# Power.net
KiCad netlist of a schematic drawn in Altium Designer
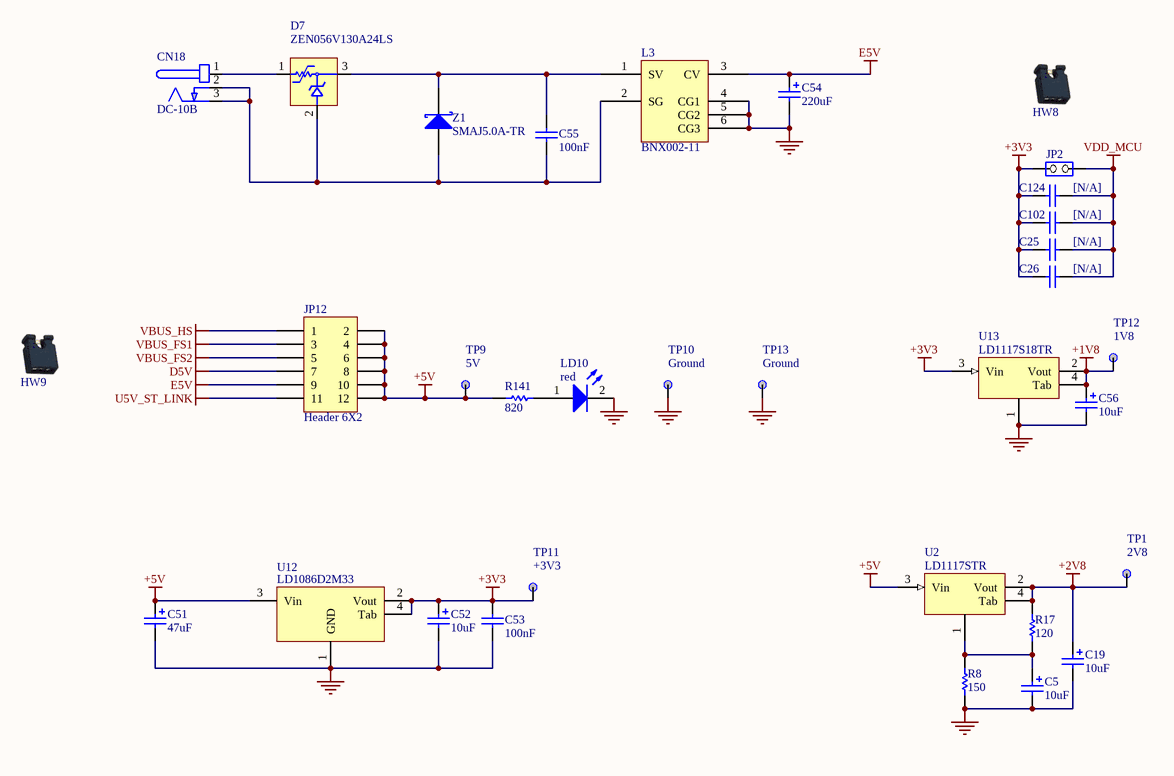
[diagram p0: Power.SchDoc]

(export (version "E")
  (design (tool "Eeschema 10.0.6"))
  (components
    (comp (ref "C5")
      (value "10uF")
      (footprint "TAN-A")
      (description "Polarized Capacitor (Radial)")
      (fields (field (name "PUBLISHER") "Altium Limited"))
      (libsource (lib "Miscellaneous Devices") (part "Cap Pol1"))
    )
    (comp (ref "C19")
      (value "10uF")
      (footprint "TAN-A")
      (description "Polarized Capacitor (Radial)")
      (fields (field (name "PUBLISHER") "Altium Limited"))
      (libsource (lib "Miscellaneous Devices") (part "Cap Pol1"))
    )
    (comp (ref "C25")
      (value "[N/A]")
      (footprint "0603C")
      (description "Capacitor")
      (fields (field (name "PUBLISHER") "Altium Limited"))
      (libsource (lib "Miscellaneous Devices") (part "Cap"))
    )
    (comp (ref "C26")
      (value "[N/A]")
      (footprint "0603C")
      (description "Capacitor")
      (fields (field (name "PUBLISHER") "Altium Limited"))
      (libsource (lib "Miscellaneous Devices") (part "Cap"))
    )
    (comp (ref "C51")
      (value "47uF")
      (footprint "CAE_5R3X5R3_H5R4")
      (description "Polarized Capacitor (Radial)")
      (fields (field (name "PUBLISHER") "Altium Limited"))
      (libsource (lib "Miscellaneous Devices") (part "Cap Pol1"))
    )
    (comp (ref "C52")
      (value "10uF")
      (footprint "TAN-A")
      (description "Polarized Capacitor (Radial)")
      (fields (field (name "PUBLISHER") "Altium Limited"))
      (libsource (lib "Miscellaneous Devices") (part "Cap Pol1"))
    )
    (comp (ref "C53")
      (value "100nF")
      (footprint "0603C")
      (description "Capacitor")
      (fields (field (name "PUBLISHER") "Altium Limited"))
      (libsource (lib "Miscellaneous Devices") (part "Cap"))
    )
    (comp (ref "C54")
      (value "220uF")
      (footprint "c310m-6")
      (description "Polarized Capacitor (Radial)")
      (fields (field (name "PUBLISHER") "Altium Limited"))
      (libsource (lib "Miscellaneous Devices") (part "Cap Pol1"))
    )
    (comp (ref "C55")
      (value "100nF")
      (footprint "0603C")
      (description "Capacitor")
      (fields (field (name "PUBLISHER") "Altium Limited"))
      (libsource (lib "Miscellaneous Devices") (part "CAP"))
    )
    (comp (ref "C56")
      (value "10uF")
      (footprint "TAN-A")
      (description "Polarized Capacitor (Radial)")
      (fields (field (name "PUBLISHER") "Altium Limited"))
      (libsource (lib "Miscellaneous Devices") (part "Cap Pol1"))
    )
    (comp (ref "C102")
      (value "[N/A]")
      (footprint "0603C")
      (description "Capacitor")
      (fields (field (name "PUBLISHER") "Altium Limited"))
      (libsource (lib "Miscellaneous Devices") (part "Cap"))
    )
    (comp (ref "C124")
      (value "[N/A]")
      (footprint "0603C")
      (description "Capacitor")
      (fields (field (name "PUBLISHER") "Altium Limited"))
      (libsource (lib "Miscellaneous Devices") (part "Cap"))
    )
    (comp (ref "CN18")
      (value "DC-10B")
      (footprint "PWR_JACK_DC10")
      (libsource (lib "STR910_SCHLIB") (part "PJ202A"))
    )
    (comp (ref "D7")
      (value "ZEN056V130A24LS")
      (footprint "TYCO_ZEN056V130A24LS")
      (libsource (lib "STR910_SCHLIB") (part "ZEN056V130A24LS"))
    )
    (comp (ref "HW8") (value "JUMPER_OPEN") (libsource (lib "mb1045") (part "JUMPER_OPEN")))
    (comp (ref "HW9") (value "JUMPER_OPEN") (libsource (lib "mb1045") (part "JUMPER_OPEN")))
    (comp (ref "JP2") (value "~") (footprint "SIP2") (libsource (lib "*") (part "JP2")))
    (comp (ref "JP12")
      (value "Header 6X2")
      (footprint "HDR_2X6_2R54")
      (description "Header, 6-Pin, Dual row")
      (fields (field (name "PUBLISHER") "Altium Limited"))
      (libsource (lib "mb1045") (part "Header 6X2"))
    )
    (comp (ref "L3")
      (value "BNX002-11")
      (footprint "BNX001")
      (description "Inductor, DC power EMI line filter, 40dB min (1MHz - 1GHz) insertion loss")
      (libsource (lib "STR910_SCHLIB") (part "BNX002"))
    )
    (comp (ref "LD10")
      (value "red")
      (footprint "0603D")
      (description "Typical RED, GREEN, YELLOW, AMBER GaAs LED")
      (fields (field (name "PUBLISHER") "Altium Limited"))
      (libsource (lib "Miscellaneous Devices") (part "LED2"))
    )
    (comp (ref "R8")
      (value "150")
      (footprint "0603R")
      (description "Resistor")
      (fields (field (name "PUBLISHER") "Altium Limited"))
      (libsource (lib "Miscellaneous Devices") (part "res1"))
    )
    (comp (ref "R17")
      (value "120")
      (footprint "0603R")
      (description "Resistor")
      (fields (field (name "PUBLISHER") "Altium Limited"))
      (libsource (lib "Miscellaneous Devices") (part "res1"))
    )
    (comp (ref "R141")
      (value "820")
      (footprint "0603R")
      (description "Resistor")
      (fields (field (name "PUBLISHER") "Altium Limited"))
      (libsource (lib "Miscellaneous Devices") (part "res1"))
    )
    (comp (ref "TP1") (value "2V8") (footprint "TP") (libsource (lib "*") (part "TP")))
    (comp (ref "TP9") (value "5V") (footprint "TP") (libsource (lib "*") (part "TP")))
    (comp (ref "TP10") (value "Ground") (footprint "TP") (libsource (lib "*") (part "TP")))
    (comp (ref "TP11") (value "+3V3") (footprint "TP") (libsource (lib "*") (part "TP")))
    (comp (ref "TP12") (value "1V8") (footprint "TP") (libsource (lib "*") (part "TP")))
    (comp (ref "TP13") (value "Ground") (footprint "TP") (libsource (lib "*") (part "TP")))
    (comp (ref "U2") (value "LD1117STR") (footprint "SOT-223") (libsource (lib "mb1045") (part "LD1117")))
    (comp (ref "U12")
      (value "LD1086D2M33")
      (footprint "TO263-3")
      (libsource (lib "mb1045") (part "VOLTREG1"))
    )
    (comp (ref "U13") (value "LD1117S18TR") (footprint "SOT-223") (libsource (lib "mb1045") (part "LD1117")))
    (comp (ref "Z1")
      (value "SMAJ5.0A-TR")
      (footprint "sma")
      (description "Schottky Diode")
      (fields (field (name "PUBLISHER") "Altium Limited"))
      (libsource (lib "Miscellaneous Devices") (part "D Schottky"))
    )
  )
  (nets
    (net (code "1") (name "+1V8") (class "Default")
      (node (ref "C56") (pin "1") (pinfunction "1_1") (pintype "passive"))
      (node (ref "TP12") (pin "1") (pinfunction "1_1") (pintype "passive"))
      (node (ref "U13") (pin "2") (pinfunction "Vout_2") (pintype "power_in"))
      (node (ref "U13") (pin "4") (pinfunction "Tab_4") (pintype "power_in"))
    )
    (net (code "2") (name "+2V8") (class "Default")
      (node (ref "C19") (pin "1") (pinfunction "1_1") (pintype "passive"))
      (node (ref "R17") (pin "1") (pinfunction "1_1") (pintype "passive"))
      (node (ref "TP1") (pin "1") (pinfunction "1_1") (pintype "passive"))
      (node (ref "U2") (pin "2") (pinfunction "Vout_2") (pintype "power_in"))
      (node (ref "U2") (pin "4") (pinfunction "Tab_4") (pintype "power_in"))
    )
    (net (code "3") (name "+3V3") (class "Default")
      (node (ref "C102") (pin "1") (pinfunction "1_1") (pintype "passive"))
      (node (ref "C124") (pin "1") (pinfunction "1_1") (pintype "passive"))
      (node (ref "C25") (pin "1") (pinfunction "1_1") (pintype "passive"))
      (node (ref "C26") (pin "1") (pinfunction "1_1") (pintype "passive"))
      (node (ref "C52") (pin "1") (pinfunction "1_1") (pintype "passive"))
      (node (ref "C53") (pin "1") (pinfunction "1_1") (pintype "passive"))
      (node (ref "JP2") (pin "1") (pinfunction "COMMON_1") (pintype "passive"))
      (node (ref "TP11") (pin "1") (pinfunction "1_1") (pintype "passive"))
      (node (ref "U12") (pin "2") (pinfunction "Vout_2") (pintype "passive"))
      (node (ref "U12") (pin "4") (pinfunction "Tab_4") (pintype "passive"))
      (node (ref "U13") (pin "3") (pinfunction "Vin_3") (pintype "input"))
    )
    (net (code "4") (name "+5V") (class "Default")
      (node (ref "C51") (pin "1") (pinfunction "1_1") (pintype "passive"))
      (node (ref "JP12") (pin "10") (pinfunction "10_10") (pintype "passive"))
      (node (ref "JP12") (pin "12") (pinfunction "12_12") (pintype "passive"))
      (node (ref "JP12") (pin "2") (pinfunction "2_2") (pintype "passive"))
      (node (ref "JP12") (pin "4") (pinfunction "4_4") (pintype "passive"))
      (node (ref "JP12") (pin "6") (pinfunction "6_6") (pintype "passive"))
      (node (ref "JP12") (pin "8") (pinfunction "8_8") (pintype "passive"))
      (node (ref "R141") (pin "2") (pinfunction "2_2") (pintype "passive"))
      (node (ref "TP9") (pin "1") (pinfunction "1_1") (pintype "passive"))
      (node (ref "U12") (pin "3") (pinfunction "Vin_3") (pintype "passive"))
      (node (ref "U2") (pin "3") (pinfunction "Vin_3") (pintype "input"))
    )
    (net (code "5") (name "D5V") (class "Default")
      (node (ref "JP12") (pin "7") (pinfunction "7_7") (pintype "passive"))
    )
    (net (code "6") (name "E5V") (class "Default")
      (node (ref "C54") (pin "1") (pinfunction "1_1") (pintype "passive"))
      (node (ref "JP12") (pin "9") (pinfunction "9_9") (pintype "passive"))
      (node (ref "L3") (pin "3") (pinfunction "CV_3") (pintype "passive"))
    )
    (net (code "7") (name "GND") (class "Default")
      (node (ref "C19") (pin "2") (pinfunction "2_2") (pintype "passive"))
      (node (ref "C5") (pin "2") (pinfunction "2_2") (pintype "passive"))
      (node (ref "C51") (pin "2") (pinfunction "2_2") (pintype "passive"))
      (node (ref "C52") (pin "2") (pinfunction "2_2") (pintype "passive"))
      (node (ref "C53") (pin "2") (pinfunction "2_2") (pintype "passive"))
      (node (ref "C54") (pin "2") (pinfunction "2_2") (pintype "passive"))
      (node (ref "C56") (pin "2") (pinfunction "2_2") (pintype "passive"))
      (node (ref "L3") (pin "4") (pinfunction "CG1_4") (pintype "passive"))
      (node (ref "L3") (pin "5") (pinfunction "CG2_5") (pintype "passive"))
      (node (ref "L3") (pin "6") (pinfunction "CG3_6") (pintype "passive"))
      (node (ref "LD10") (pin "2") (pinfunction "K_2") (pintype "passive"))
      (node (ref "R8") (pin "2") (pinfunction "2_2") (pintype "passive"))
      (node (ref "TP10") (pin "1") (pinfunction "1_1") (pintype "passive"))
      (node (ref "TP13") (pin "1") (pinfunction "1_1") (pintype "passive"))
      (node (ref "U12") (pin "1") (pinfunction "GND_1") (pintype "passive"))
      (node (ref "U13") (pin "1") (pintype "passive"))
    )
    (net (code "8") (name "Net-(C5-Pad1)") (class "Default")
      (node (ref "C5") (pin "1") (pinfunction "1_1") (pintype "passive"))
      (node (ref "R17") (pin "2") (pinfunction "2_2") (pintype "passive"))
      (node (ref "R8") (pin "1") (pinfunction "1_1") (pintype "passive"))
      (node (ref "U2") (pin "1") (pintype "passive"))
    )
    (net (code "9") (name "Net-(CN18-+)") (class "Default")
      (node (ref "CN18") (pin "1") (pinfunction "+_1") (pintype "passive"))
      (node (ref "D7") (pin "1") (pintype "passive"))
    )
    (net (code "10") (name "Net-(L3-SG)") (class "Default")
      (node (ref "C55") (pin "2") (pinfunction "2_2") (pintype "passive"))
      (node (ref "CN18") (pin "2") (pinfunction "GND_2") (pintype "passive"))
      (node (ref "CN18") (pin "3") (pinfunction "GND_3") (pintype "passive"))
      (node (ref "D7") (pin "2") (pintype "passive"))
      (node (ref "L3") (pin "2") (pinfunction "SG_2") (pintype "passive"))
      (node (ref "Z1") (pin "1") (pinfunction "A_1") (pintype "passive"))
    )
    (net (code "11") (name "Net-(L3-SV)") (class "Default")
      (node (ref "C55") (pin "1") (pinfunction "1_1") (pintype "passive"))
      (node (ref "D7") (pin "3") (pintype "passive"))
      (node (ref "L3") (pin "1") (pinfunction "SV_1") (pintype "passive"))
      (node (ref "Z1") (pin "2") (pinfunction "K_2") (pintype "passive"))
    )
    (net (code "12") (name "Net-(LD10-A)") (class "Default")
      (node (ref "LD10") (pin "1") (pinfunction "A_1") (pintype "passive"))
      (node (ref "R141") (pin "1") (pinfunction "1_1") (pintype "passive"))
    )
    (net (code "13") (name "U5V_ST_LINK") (class "Default")
      (node (ref "JP12") (pin "11") (pinfunction "11_11") (pintype "passive"))
    )
    (net (code "14") (name "VBUS_FS1") (class "Default")
      (node (ref "JP12") (pin "3") (pinfunction "3_3") (pintype "passive"))
    )
    (net (code "15") (name "VBUS_FS2") (class "Default")
      (node (ref "JP12") (pin "5") (pinfunction "5_5") (pintype "passive"))
    )
    (net (code "16") (name "VBUS_HS") (class "Default")
      (node (ref "JP12") (pin "1") (pinfunction "1_1") (pintype "passive"))
    )
    (net (code "17") (name "VDD_MCU") (class "Default")
      (node (ref "C102") (pin "2") (pinfunction "2_2") (pintype "passive"))
      (node (ref "C124") (pin "2") (pinfunction "2_2") (pintype "passive"))
      (node (ref "C25") (pin "2") (pinfunction "2_2") (pintype "passive"))
      (node (ref "C26") (pin "2") (pinfunction "2_2") (pintype "passive"))
      (node (ref "JP2") (pin "2") (pinfunction "NO_2") (pintype "passive"))
    )
  )
)
